# ad.net
KiCad netlist of a schematic drawn in Altium Designer
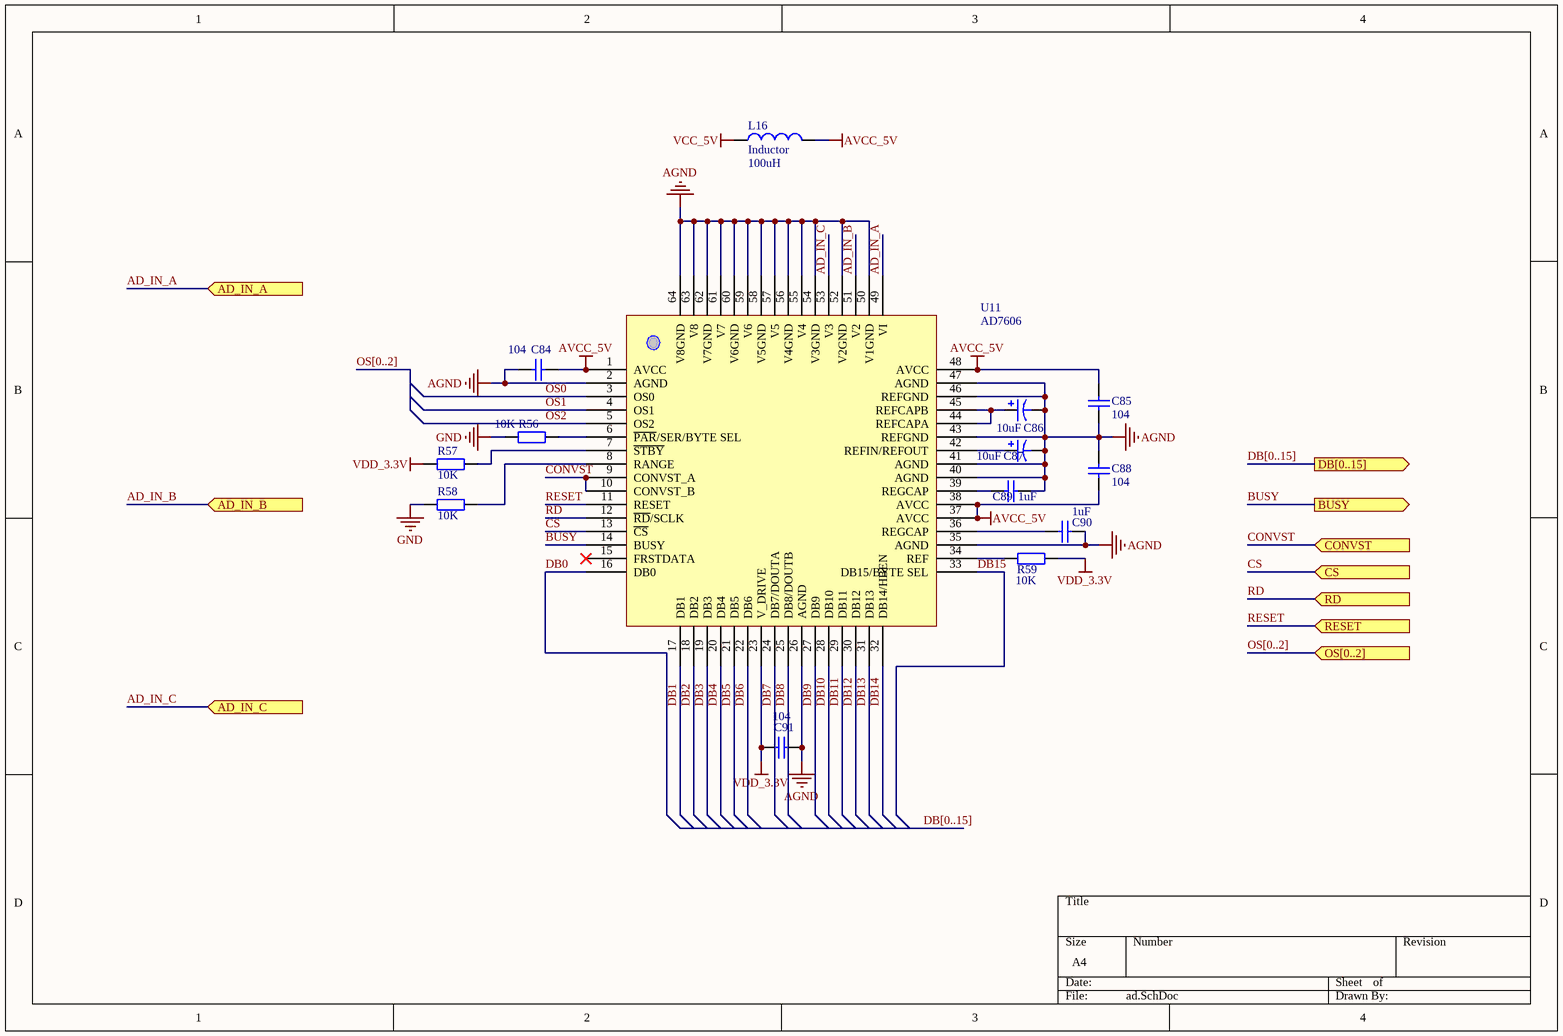
[diagram p0: ad.SchDoc]

(export (version "E")
  (design (tool "Eeschema 10.0.6"))
  (components
    (comp (ref "C84")
      (value "104")
      (footprint "0805")
      (fields
        (field (name "Comment") "Cap")
        (field (name "原理图绘制者") "刘永钦")
        (field (name "原理图提供者") "刘永钦")
        (field (name "原理图审核人1") "徐鹏飞")
        (field (name "封装0805绘制者") "刘永钦")
        (field (name "封装0805提供者") "刘永钦")
        (field (name "封装0805审核人1") "徐鹏飞")
        (field (name "原理图审核人2") "朱觉文")
        (field (name "封装0805审核人2") "朱觉文")
        (field (name "封装0603绘制者") "刘永钦")
        (field (name "封装0603提供者") "刘永钦")
        (field (name "封装0603审核人1") "朱觉文")
        (field (name "封装0603审核人2") "徐鹏飞")
      )
      (libsource (lib "自动化研究所集成库20170318") (part "Cap"))
    )
    (comp (ref "C85")
      (value "104")
      (footprint "0805")
      (fields
        (field (name "Comment") "Cap")
        (field (name "原理图绘制者") "刘永钦")
        (field (name "原理图提供者") "刘永钦")
        (field (name "原理图审核人1") "徐鹏飞")
        (field (name "封装0805绘制者") "刘永钦")
        (field (name "封装0805提供者") "刘永钦")
        (field (name "封装0805审核人1") "徐鹏飞")
        (field (name "原理图审核人2") "朱觉文")
        (field (name "封装0805审核人2") "朱觉文")
        (field (name "封装0603绘制者") "刘永钦")
        (field (name "封装0603提供者") "刘永钦")
        (field (name "封装0603审核人1") "朱觉文")
        (field (name "封装0603审核人2") "徐鹏飞")
      )
      (libsource (lib "自动化研究所集成库20170318") (part "Cap"))
    )
    (comp (ref "C86")
      (value "10uF")
      (footprint "Cap 3528B")
      (fields
        (field (name "Comment") "Cap Poll")
        (field (name "原理图绘制者") "刘永钦")
        (field (name "原理图提供者") "刘永钦")
        (field (name "原理图审核人1") "徐鹏飞")
        (field (name "封装CAP 钽 7343 E绘制者") "刘永钦")
        (field (name "封装CAP 钽 7343 E提供者") "刘永钦")
        (field (name "封装CAP 钽 7343 E审核人1") "徐鹏飞")
        (field (name "封装CAP贴片铝电解质470UF 16V绘制者") "李泽")
        (field (name "封装CAP贴片铝电解质470UF 16V提供者") "刘永钦")
        (field (name "封装CAP贴片铝电解质470UF 16V审核人1") "徐鹏飞")
        (field (name "封装CAP 3528B绘制者") "陈汉诚")
        (field (name "封装CAP 3528B提供者") "刘永钦")
        (field (name "封装CAP 3528B审核人1") "徐鹏飞")
        (field (name "封装CAP直插 10UF 50V提供者") "刘永钦")
        (field (name "封装CAP直插 10UF 50V审核人1") "徐鹏飞")
        (field (name "封装CAP 3528B审核人2") "朱觉文")
        (field (name "封装CAP直插 10UF 50V审核人2") "朱觉文")
        (field (name "封装CAP贴片铝电解质470UF 16V审核人2") "朱觉文")
        (field (name "封装CAP 钽 7343 E审核人2") "朱觉文")
        (field (name "原理图审核人2") "朱觉文")
      )
      (libsource (lib "自动化研究所集成库20170318") (part "Cap Poll"))
    )
    (comp (ref "C87")
      (value "10uF")
      (footprint "Cap 3528B")
      (fields
        (field (name "Comment") "Cap Poll")
        (field (name "原理图绘制者") "刘永钦")
        (field (name "原理图提供者") "刘永钦")
        (field (name "原理图审核人1") "徐鹏飞")
        (field (name "封装CAP 钽 7343 E绘制者") "刘永钦")
        (field (name "封装CAP 钽 7343 E提供者") "刘永钦")
        (field (name "封装CAP 钽 7343 E审核人1") "徐鹏飞")
        (field (name "封装CAP贴片铝电解质470UF 16V绘制者") "李泽")
        (field (name "封装CAP贴片铝电解质470UF 16V提供者") "刘永钦")
        (field (name "封装CAP贴片铝电解质470UF 16V审核人1") "徐鹏飞")
        (field (name "封装CAP 3528B绘制者") "陈汉诚")
        (field (name "封装CAP 3528B提供者") "刘永钦")
        (field (name "封装CAP 3528B审核人1") "徐鹏飞")
        (field (name "封装CAP直插 10UF 50V提供者") "刘永钦")
        (field (name "封装CAP直插 10UF 50V审核人1") "徐鹏飞")
        (field (name "封装CAP 3528B审核人2") "朱觉文")
        (field (name "封装CAP直插 10UF 50V审核人2") "朱觉文")
        (field (name "封装CAP贴片铝电解质470UF 16V审核人2") "朱觉文")
        (field (name "封装CAP 钽 7343 E审核人2") "朱觉文")
        (field (name "原理图审核人2") "朱觉文")
      )
      (libsource (lib "自动化研究所集成库20170318") (part "Cap Poll"))
    )
    (comp (ref "C88")
      (value "104")
      (footprint "0805")
      (fields
        (field (name "Comment") "Cap")
        (field (name "原理图绘制者") "刘永钦")
        (field (name "原理图提供者") "刘永钦")
        (field (name "原理图审核人1") "徐鹏飞")
        (field (name "封装0805绘制者") "刘永钦")
        (field (name "封装0805提供者") "刘永钦")
        (field (name "封装0805审核人1") "徐鹏飞")
        (field (name "原理图审核人2") "朱觉文")
        (field (name "封装0805审核人2") "朱觉文")
        (field (name "封装0603绘制者") "刘永钦")
        (field (name "封装0603提供者") "刘永钦")
        (field (name "封装0603审核人1") "朱觉文")
        (field (name "封装0603审核人2") "徐鹏飞")
      )
      (libsource (lib "自动化研究所集成库20170318") (part "Cap"))
    )
    (comp (ref "C89")
      (value "1uF")
      (footprint "0805")
      (fields
        (field (name "Comment") "Cap")
        (field (name "原理图绘制者") "刘永钦")
        (field (name "原理图提供者") "刘永钦")
        (field (name "原理图审核人1") "徐鹏飞")
        (field (name "封装0805绘制者") "刘永钦")
        (field (name "封装0805提供者") "刘永钦")
        (field (name "封装0805审核人1") "徐鹏飞")
        (field (name "原理图审核人2") "朱觉文")
        (field (name "封装0805审核人2") "朱觉文")
        (field (name "封装0603绘制者") "刘永钦")
        (field (name "封装0603提供者") "刘永钦")
        (field (name "封装0603审核人1") "朱觉文")
        (field (name "封装0603审核人2") "徐鹏飞")
      )
      (libsource (lib "自动化研究所集成库20170318") (part "Cap"))
    )
    (comp (ref "C90")
      (value "1uF")
      (footprint "0805")
      (fields
        (field (name "Comment") "Cap")
        (field (name "原理图绘制者") "刘永钦")
        (field (name "原理图提供者") "刘永钦")
        (field (name "原理图审核人1") "徐鹏飞")
        (field (name "封装0805绘制者") "刘永钦")
        (field (name "封装0805提供者") "刘永钦")
        (field (name "封装0805审核人1") "徐鹏飞")
        (field (name "原理图审核人2") "朱觉文")
        (field (name "封装0805审核人2") "朱觉文")
        (field (name "封装0603绘制者") "刘永钦")
        (field (name "封装0603提供者") "刘永钦")
        (field (name "封装0603审核人1") "朱觉文")
        (field (name "封装0603审核人2") "徐鹏飞")
      )
      (libsource (lib "自动化研究所集成库20170318") (part "Cap"))
    )
    (comp (ref "C91")
      (value "104")
      (footprint "0805")
      (fields
        (field (name "Comment") "Cap")
        (field (name "原理图绘制者") "刘永钦")
        (field (name "原理图提供者") "刘永钦")
        (field (name "原理图审核人1") "徐鹏飞")
        (field (name "封装0805绘制者") "刘永钦")
        (field (name "封装0805提供者") "刘永钦")
        (field (name "封装0805审核人1") "徐鹏飞")
        (field (name "原理图审核人2") "朱觉文")
        (field (name "封装0805审核人2") "朱觉文")
        (field (name "封装0603绘制者") "刘永钦")
        (field (name "封装0603提供者") "刘永钦")
        (field (name "封装0603审核人1") "朱觉文")
        (field (name "封装0603审核人2") "徐鹏飞")
      )
      (libsource (lib "自动化研究所集成库20170318") (part "Cap"))
    )
    (comp (ref "L16")
      (value "Inductor")
      (footprint "0805_Inductor")
      (fields
        (field (name "ALTIUM_VALUE") "100uH")
        (field (name "原理图绘制者") "刘永钦")
        (field (name "原理图提供者") "刘永钦")
        (field (name "原理图审核人1") "徐鹏飞")
        (field (name "封装0805_INDUCTOR绘制者") "未知")
        (field (name "封装0805_INDUCTOR提供者") "刘永钦")
        (field (name "封装0805_INDUCTOR审核人1") "徐鹏飞")
        (field (name "原理图审核人2") "朱觉文")
        (field (name "封装0805_INDUCTOR审核人2") "朱觉文")
      )
      (libsource (lib "自动化研究所集成库20170318") (part "Inductor"))
    )
    (comp (ref "R56")
      (value "10K")
      (footprint "0805")
      (fields
        (field (name "Comment") "Res")
        (field (name "原理图绘制者") "刘永钦")
        (field (name "原理图提供者") "刘永钦")
        (field (name "原理图审核人1") "徐鹏飞")
        (field (name "封装0805绘制者") "刘永钦")
        (field (name "封装0805提供者") "刘永钦")
        (field (name "封装0805审核人1") "徐鹏飞")
        (field (name "原理图审核人2") "朱觉文")
        (field (name "封装0805审核人2") "朱觉文")
        (field (name "封装0603提供者") "刘永钦")
        (field (name "封装0603审核人2") "朱觉文")
        (field (name "封装0603审核人1") "徐鹏飞")
        (field (name "封装2512-RESC6332X06N审核人2") "朱觉文")
        (field (name "封装2512-RESC6332X06N提供者") "刘永钦")
        (field (name "封装2512-RESC6332X06N审核人1") "徐鹏飞")
        (field (name "封装0603绘制者") "刘永钦")
        (field (name "封装2512-RESC6332X06N绘制者") "刘永钦")
      )
      (libsource (lib "自动化研究所集成库20170318") (part "Res"))
    )
    (comp (ref "R57")
      (value "10K")
      (footprint "0805")
      (fields
        (field (name "Comment") "Res")
        (field (name "原理图绘制者") "刘永钦")
        (field (name "原理图提供者") "刘永钦")
        (field (name "原理图审核人1") "徐鹏飞")
        (field (name "封装0805绘制者") "刘永钦")
        (field (name "封装0805提供者") "刘永钦")
        (field (name "封装0805审核人1") "徐鹏飞")
        (field (name "原理图审核人2") "朱觉文")
        (field (name "封装0805审核人2") "朱觉文")
        (field (name "封装0603提供者") "刘永钦")
        (field (name "封装0603审核人2") "朱觉文")
        (field (name "封装0603审核人1") "徐鹏飞")
        (field (name "封装2512-RESC6332X06N审核人2") "朱觉文")
        (field (name "封装2512-RESC6332X06N提供者") "刘永钦")
        (field (name "封装2512-RESC6332X06N审核人1") "徐鹏飞")
        (field (name "封装0603绘制者") "刘永钦")
        (field (name "封装2512-RESC6332X06N绘制者") "刘永钦")
      )
      (libsource (lib "自动化研究所集成库20170318") (part "Res"))
    )
    (comp (ref "R58")
      (value "10K")
      (footprint "0805")
      (fields
        (field (name "Comment") "Res")
        (field (name "原理图绘制者") "刘永钦")
        (field (name "原理图提供者") "刘永钦")
        (field (name "原理图审核人1") "徐鹏飞")
        (field (name "封装0805绘制者") "刘永钦")
        (field (name "封装0805提供者") "刘永钦")
        (field (name "封装0805审核人1") "徐鹏飞")
        (field (name "原理图审核人2") "朱觉文")
        (field (name "封装0805审核人2") "朱觉文")
        (field (name "封装0603提供者") "刘永钦")
        (field (name "封装0603审核人2") "朱觉文")
        (field (name "封装0603审核人1") "徐鹏飞")
        (field (name "封装2512-RESC6332X06N审核人2") "朱觉文")
        (field (name "封装2512-RESC6332X06N提供者") "刘永钦")
        (field (name "封装2512-RESC6332X06N审核人1") "徐鹏飞")
        (field (name "封装0603绘制者") "刘永钦")
        (field (name "封装2512-RESC6332X06N绘制者") "刘永钦")
      )
      (libsource (lib "自动化研究所集成库20170318") (part "Res"))
    )
    (comp (ref "R59")
      (value "10K")
      (footprint "0805")
      (fields
        (field (name "Comment") "Res")
        (field (name "原理图绘制者") "刘永钦")
        (field (name "原理图提供者") "刘永钦")
        (field (name "原理图审核人1") "徐鹏飞")
        (field (name "封装0805绘制者") "刘永钦")
        (field (name "封装0805提供者") "刘永钦")
        (field (name "封装0805审核人1") "徐鹏飞")
        (field (name "原理图审核人2") "朱觉文")
        (field (name "封装0805审核人2") "朱觉文")
        (field (name "封装0603提供者") "刘永钦")
        (field (name "封装0603审核人2") "朱觉文")
        (field (name "封装0603审核人1") "徐鹏飞")
        (field (name "封装2512-RESC6332X06N审核人2") "朱觉文")
        (field (name "封装2512-RESC6332X06N提供者") "刘永钦")
        (field (name "封装2512-RESC6332X06N审核人1") "徐鹏飞")
        (field (name "封装0603绘制者") "刘永钦")
        (field (name "封装2512-RESC6332X06N绘制者") "刘永钦")
      )
      (libsource (lib "自动化研究所集成库20170318") (part "Res"))
    )
    (comp (ref "U11")
      (value "AD7606")
      (footprint "TSQFP50P1200X1200X160-64N")
      (libsource (lib "Dugu") (part "AD7606"))
    )
  )
  (nets
    (net (code "1") (name "/AD_IN_A") (class "Default")
      (node (ref "U11") (pin "49") (pinfunction "VI_49") (pintype "passive"))
    )
    (net (code "2") (name "/AD_IN_B") (class "Default")
      (node (ref "U11") (pin "51") (pinfunction "V2_51") (pintype "passive"))
    )
    (net (code "3") (name "/AD_IN_C") (class "Default")
      (node (ref "U11") (pin "53") (pinfunction "V3_53") (pintype "passive"))
    )
    (net (code "4") (name "/BUSY") (class "Default")
      (node (ref "U11") (pin "14") (pinfunction "BUSY_14") (pintype "passive"))
    )
    (net (code "5") (name "/CONVST") (class "Default")
      (node (ref "U11") (pin "10") (pinfunction "CONVST_B_10") (pintype "passive"))
      (node (ref "U11") (pin "9") (pinfunction "CONVST_A_9") (pintype "passive"))
    )
    (net (code "6") (name "/CS") (class "Default")
      (node (ref "U11") (pin "13") (pinfunction "~{CS}_13") (pintype "passive"))
    )
    (net (code "7") (name "/DB0") (class "Default")
      (node (ref "U11") (pin "16") (pinfunction "DB0_16") (pintype "passive"))
    )
    (net (code "8") (name "/DB1") (class "Default")
      (node (ref "U11") (pin "17") (pinfunction "DB1_17") (pintype "passive"))
    )
    (net (code "9") (name "/DB2") (class "Default")
      (node (ref "U11") (pin "18") (pinfunction "DB2_18") (pintype "passive"))
    )
    (net (code "10") (name "/DB3") (class "Default")
      (node (ref "U11") (pin "19") (pinfunction "DB3_19") (pintype "passive"))
    )
    (net (code "11") (name "/DB4") (class "Default")
      (node (ref "U11") (pin "20") (pinfunction "DB4_20") (pintype "passive"))
    )
    (net (code "12") (name "/DB5") (class "Default")
      (node (ref "U11") (pin "21") (pinfunction "DB5_21") (pintype "passive"))
    )
    (net (code "13") (name "/DB6") (class "Default")
      (node (ref "U11") (pin "22") (pinfunction "DB6_22") (pintype "passive"))
    )
    (net (code "14") (name "/DB7") (class "Default")
      (node (ref "U11") (pin "24") (pinfunction "DB7/DOUTA_24") (pintype "passive"))
    )
    (net (code "15") (name "/DB8") (class "Default")
      (node (ref "U11") (pin "25") (pinfunction "DB8/DOUTB_25") (pintype "passive"))
    )
    (net (code "16") (name "/DB9") (class "Default")
      (node (ref "U11") (pin "27") (pinfunction "DB9_27") (pintype "passive"))
    )
    (net (code "17") (name "/DB10") (class "Default")
      (node (ref "U11") (pin "28") (pinfunction "DB10_28") (pintype "passive"))
    )
    (net (code "18") (name "/DB11") (class "Default")
      (node (ref "U11") (pin "29") (pinfunction "DB11_29") (pintype "passive"))
    )
    (net (code "19") (name "/DB12") (class "Default")
      (node (ref "U11") (pin "30") (pinfunction "DB12_30") (pintype "passive"))
    )
    (net (code "20") (name "/DB13") (class "Default")
      (node (ref "U11") (pin "31") (pinfunction "DB13_31") (pintype "passive"))
    )
    (net (code "21") (name "/DB14") (class "Default")
      (node (ref "U11") (pin "32") (pinfunction "DB14/HBEN_32") (pintype "passive"))
    )
    (net (code "22") (name "/DB15") (class "Default")
      (node (ref "U11") (pin "33") (pinfunction "DB15/BYTE_SEL_33") (pintype "passive"))
    )
    (net (code "24") (name "/OS0") (class "Default")
      (node (ref "U11") (pin "3") (pinfunction "OS0_3") (pintype "passive"))
    )
    (net (code "25") (name "/OS1") (class "Default")
      (node (ref "U11") (pin "4") (pinfunction "OS1_4") (pintype "passive"))
    )
    (net (code "26") (name "/OS2") (class "Default")
      (node (ref "U11") (pin "5") (pinfunction "OS2_5") (pintype "passive"))
    )
    (net (code "28") (name "/RD") (class "Default")
      (node (ref "U11") (pin "12") (pinfunction "~{RD}/SCLK_12") (pintype "passive"))
    )
    (net (code "29") (name "/RESET") (class "Default")
      (node (ref "U11") (pin "11") (pinfunction "RESET_11") (pintype "passive"))
    )
    (net (code "30") (name "AGND") (class "Default")
      (node (ref "C84") (pin "2") (pinfunction "2_2") (pintype "passive"))
      (node (ref "C85") (pin "2") (pinfunction "2_2") (pintype "passive"))
      (node (ref "C86") (pin "2") (pinfunction "2_2") (pintype "passive"))
      (node (ref "C87") (pin "2") (pinfunction "2_2") (pintype "passive"))
      (node (ref "C88") (pin "1") (pinfunction "1_1") (pintype "passive"))
      (node (ref "C89") (pin "1") (pinfunction "1_1") (pintype "passive"))
      (node (ref "C90") (pin "1") (pinfunction "1_1") (pintype "passive"))
      (node (ref "C91") (pin "1") (pinfunction "1_1") (pintype "passive"))
      (node (ref "U11") (pin "2") (pinfunction "AGND_2") (pintype "passive"))
      (node (ref "U11") (pin "26") (pinfunction "AGND_26") (pintype "passive"))
      (node (ref "U11") (pin "35") (pinfunction "AGND_35") (pintype "passive"))
      (node (ref "U11") (pin "40") (pinfunction "AGND_40") (pintype "passive"))
      (node (ref "U11") (pin "41") (pinfunction "AGND_41") (pintype "passive"))
      (node (ref "U11") (pin "43") (pinfunction "REFGND_43") (pintype "passive"))
      (node (ref "U11") (pin "46") (pinfunction "REFGND_46") (pintype "passive"))
      (node (ref "U11") (pin "47") (pinfunction "AGND_47") (pintype "passive"))
      (node (ref "U11") (pin "50") (pinfunction "V1GND_50") (pintype "passive"))
      (node (ref "U11") (pin "52") (pinfunction "V2GND_52") (pintype "passive"))
      (node (ref "U11") (pin "54") (pinfunction "V3GND_54") (pintype "passive"))
      (node (ref "U11") (pin "55") (pinfunction "V4_55") (pintype "passive"))
      (node (ref "U11") (pin "56") (pinfunction "V4GND_56") (pintype "passive"))
      (node (ref "U11") (pin "57") (pinfunction "V5_57") (pintype "passive"))
      (node (ref "U11") (pin "58") (pinfunction "V5GND_58") (pintype "passive"))
      (node (ref "U11") (pin "59") (pinfunction "V6_59") (pintype "passive"))
      (node (ref "U11") (pin "60") (pinfunction "V6GND_60") (pintype "passive"))
      (node (ref "U11") (pin "61") (pinfunction "V7_61") (pintype "passive"))
      (node (ref "U11") (pin "62") (pinfunction "V7GND_62") (pintype "passive"))
      (node (ref "U11") (pin "63") (pinfunction "V8_63") (pintype "passive"))
      (node (ref "U11") (pin "64") (pinfunction "V8GND_64") (pintype "passive"))
    )
    (net (code "31") (name "AVCC_5V") (class "Default")
      (node (ref "C84") (pin "1") (pinfunction "1_1") (pintype "passive"))
      (node (ref "C85") (pin "1") (pinfunction "1_1") (pintype "passive"))
      (node (ref "C88") (pin "2") (pinfunction "2_2") (pintype "passive"))
      (node (ref "L16") (pin "2") (pinfunction "2_2") (pintype "passive"))
      (node (ref "U11") (pin "1") (pinfunction "AVCC_1") (pintype "passive"))
      (node (ref "U11") (pin "37") (pinfunction "AVCC_37") (pintype "passive"))
      (node (ref "U11") (pin "38") (pinfunction "AVCC_38") (pintype "passive"))
      (node (ref "U11") (pin "48") (pinfunction "AVCC_48") (pintype "passive"))
    )
    (net (code "32") (name "GND") (class "Default")
      (node (ref "R56") (pin "1") (pinfunction "1_1") (pintype "passive"))
      (node (ref "R58") (pin "1") (pinfunction "1_1") (pintype "passive"))
    )
    (net (code "33") (name "Net-(C89-Pad2)") (class "Default")
      (node (ref "C89") (pin "2") (pinfunction "2_2") (pintype "passive"))
      (node (ref "U11") (pin "39") (pinfunction "REGCAP_39") (pintype "passive"))
    )
    (net (code "34") (name "Net-(C90-Pad2)") (class "Default")
      (node (ref "C90") (pin "2") (pinfunction "2_2") (pintype "passive"))
      (node (ref "U11") (pin "36") (pinfunction "REGCAP_36") (pintype "passive"))
    )
    (net (code "35") (name "Net-(U11-RANGE)") (class "Default")
      (node (ref "R58") (pin "2") (pinfunction "2_2") (pintype "passive"))
      (node (ref "U11") (pin "8") (pinfunction "RANGE_8") (pintype "passive"))
    )
    (net (code "36") (name "Net-(U11-REF)") (class "Default")
      (node (ref "R59") (pin "1") (pinfunction "1_1") (pintype "passive"))
      (node (ref "U11") (pin "34") (pinfunction "REF_34") (pintype "passive"))
    )
    (net (code "37") (name "Net-(U11-REFCAPA)") (class "Default")
      (node (ref "C86") (pin "1") (pinfunction "1_1") (pintype "passive"))
      (node (ref "U11") (pin "44") (pinfunction "REFCAPA_44") (pintype "passive"))
      (node (ref "U11") (pin "45") (pinfunction "REFCAPB_45") (pintype "passive"))
    )
    (net (code "38") (name "Net-(U11-REFIN{slash}REFOUT)") (class "Default")
      (node (ref "C87") (pin "1") (pinfunction "1_1") (pintype "passive"))
      (node (ref "U11") (pin "42") (pinfunction "REFIN/REFOUT_42") (pintype "passive"))
    )
    (net (code "39") (name "Net-(U11-~{PAR}{slash}SER{slash}BYTE_SEL)") (class "Default")
      (node (ref "R56") (pin "2") (pinfunction "2_2") (pintype "passive"))
      (node (ref "U11") (pin "6") (pinfunction "~{PAR}/SER/BYTE_SEL_6") (pintype "passive"))
    )
    (net (code "40") (name "Net-(U11-~{STBY})") (class "Default")
      (node (ref "R57") (pin "2") (pinfunction "2_2") (pintype "passive"))
      (node (ref "U11") (pin "7") (pinfunction "~{STBY}_7") (pintype "passive"))
    )
    (net (code "41") (name "VCC_5V") (class "Default")
      (node (ref "L16") (pin "1") (pinfunction "1_1") (pintype "passive"))
    )
    (net (code "42") (name "VDD_3.3V") (class "Default")
      (node (ref "C91") (pin "2") (pinfunction "2_2") (pintype "passive"))
      (node (ref "R57") (pin "1") (pinfunction "1_1") (pintype "passive"))
      (node (ref "R59") (pin "2") (pinfunction "2_2") (pintype "passive"))
      (node (ref "U11") (pin "23") (pinfunction "V_DRIVE_23") (pintype "passive"))
    )
    (net (code "43") (name "unconnected-(U11-FRSTDATA-Pad15)") (class "Default")
      (node (ref "U11") (pin "15") (pinfunction "FRSTDATA_15") (pintype "passive+no_connect"))
    )
  )
)
